# Morpheus_middle.net
KiCad netlist of a schematic drawn in Altium Designer
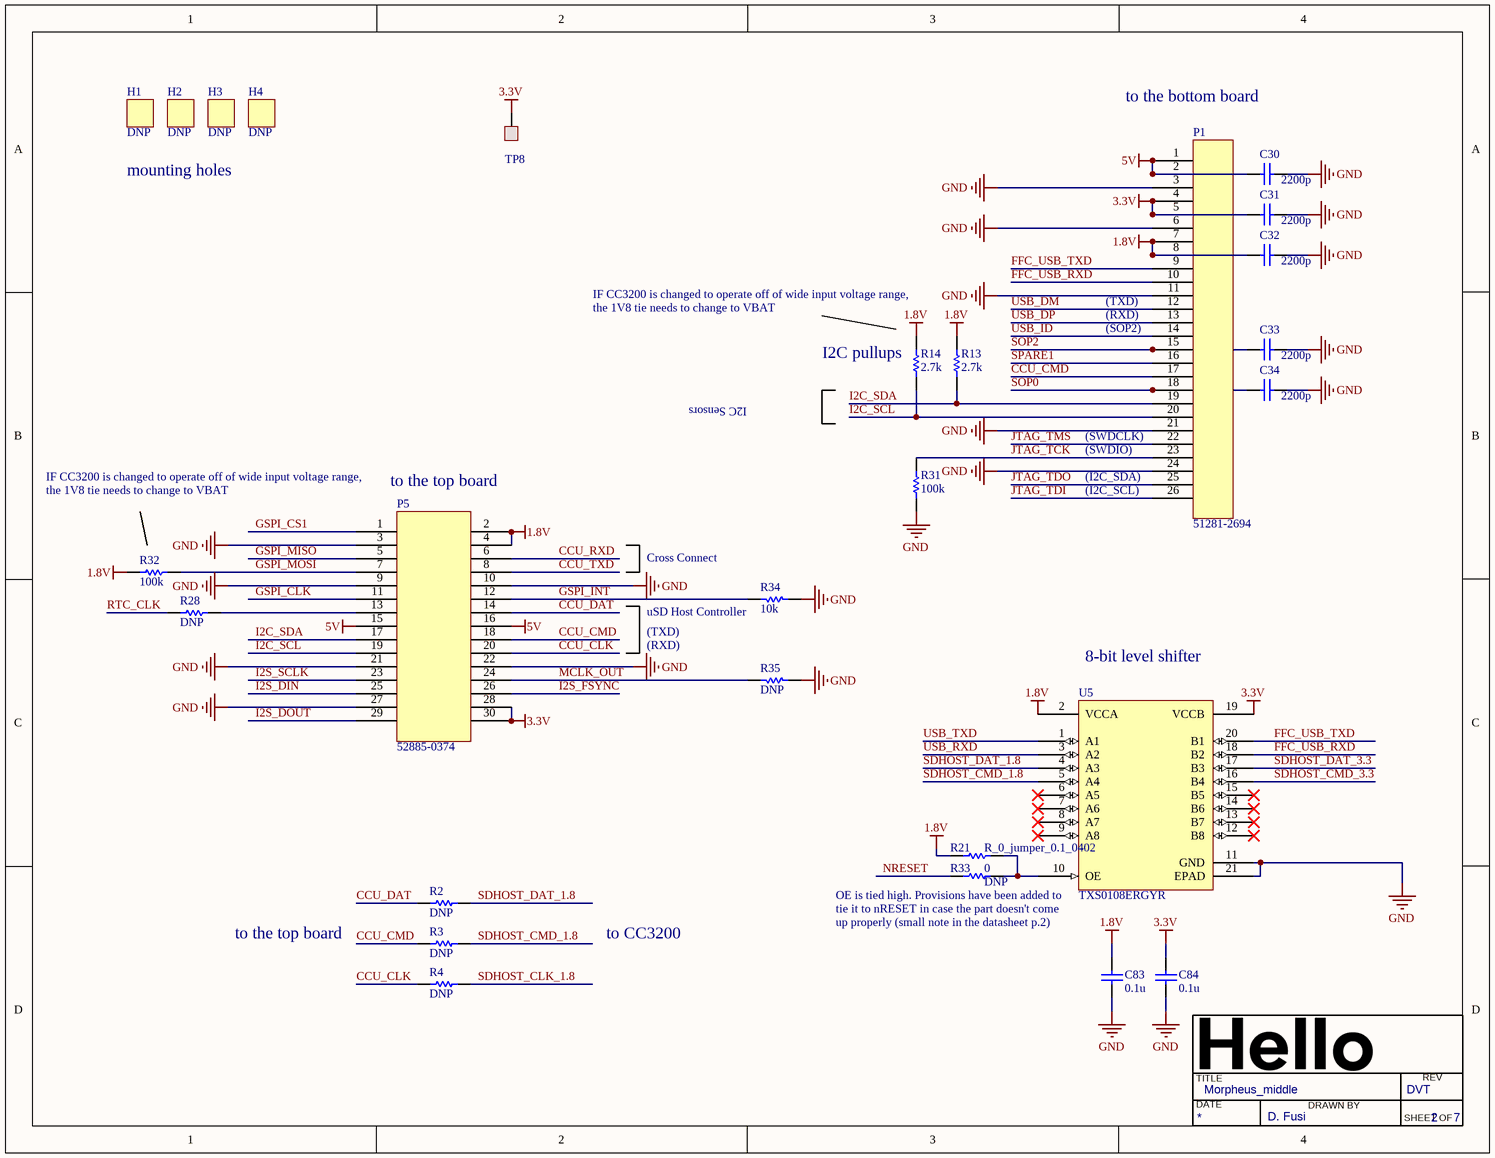
[diagram p0: Morpheus_middle.SchDoc]

(export (version "E")
  (design (tool "Eeschema 10.0.6"))
  (components
    (comp (ref "C30")
      (value "2200p")
      (footprint "CAP0402_SENSE_DVT")
      (description "Chip capacitor")
      (fields (field (name "TOLERANCE") "5 %") (field (name "VOLTAGE") "16V"))
      (libsource (lib "Morpheus_pill") (part "C_2200p_5_16_STD_0402"))
    )
    (comp (ref "C31")
      (value "2200p")
      (footprint "CAP0402_SENSE_DVT")
      (description "Chip capacitor")
      (fields (field (name "TOLERANCE") "5 %") (field (name "VOLTAGE") "16V"))
      (libsource (lib "Morpheus_pill") (part "C_2200p_5_16_STD_0402"))
    )
    (comp (ref "C32")
      (value "2200p")
      (footprint "CAP0402_SENSE_DVT")
      (description "Chip capacitor")
      (fields (field (name "TOLERANCE") "5 %") (field (name "VOLTAGE") "16V"))
      (libsource (lib "Morpheus_pill") (part "C_2200p_5_16_STD_0402"))
    )
    (comp (ref "C33")
      (value "2200p")
      (footprint "CAP0402_SENSE_DVT")
      (description "Chip capacitor")
      (fields (field (name "TOLERANCE") "5 %") (field (name "VOLTAGE") "16V"))
      (libsource (lib "Morpheus_pill") (part "C_2200p_5_16_STD_0402"))
    )
    (comp (ref "C34")
      (value "2200p")
      (footprint "CAP0402_SENSE_DVT")
      (description "Chip capacitor")
      (fields (field (name "TOLERANCE") "5 %") (field (name "VOLTAGE") "16V"))
      (libsource (lib "Morpheus_pill") (part "C_2200p_5_16_STD_0402"))
    )
    (comp (ref "C83")
      (value "0.1u")
      (footprint "CAP0402_SENSE_DVT")
      (description "Chip capacitor")
      (fields (field (name "TOLERANCE") "10%") (field (name "VOLTAGE") "50V"))
      (libsource (lib "Morpheus_pill") (part "C_0.1u_10_50_X7R_0402"))
    )
    (comp (ref "C84")
      (value "0.1u")
      (footprint "CAP0402_SENSE_DVT")
      (description "Chip capacitor")
      (fields (field (name "TOLERANCE") "10%") (field (name "VOLTAGE") "50V"))
      (libsource (lib "Morpheus_pill") (part "C_0.1u_10_50_X7R_0402"))
    )
    (comp (ref "H1")
      (value "DNP")
      (footprint "HOLE_ROUND_1.8mm")
      (description "general purpose hole")
      (libsource (lib "Morpheus_pill") (part "Hole"))
    )
    (comp (ref "H2")
      (value "DNP")
      (footprint "HOLE_ROUND_1.8mm")
      (description "general purpose hole")
      (libsource (lib "Morpheus_pill") (part "Hole"))
    )
    (comp (ref "H3")
      (value "DNP")
      (footprint "HOLE_ROUND_1.8mm")
      (description "general purpose hole")
      (libsource (lib "Morpheus_pill") (part "Hole"))
    )
    (comp (ref "H4")
      (value "DNP")
      (footprint "HOLE_ROUND_1.8mm")
      (description "general purpose hole")
      (libsource (lib "Morpheus_pill") (part "Hole"))
    )
    (comp (ref "P1")
      (value "51281-2694")
      (footprint "molex_51281-2694")
      (description "Molex 26-pin 0.5mm pitch connector")
      (libsource (lib "Morpheus_pill") (part "molex_51281-2694"))
    )
    (comp (ref "P5")
      (value "52885-0374")
      (footprint "molex_52885-0374")
      (description "Molex 30-pin 0.635mm pitch receptacle connector")
      (libsource (lib "Morpheus_pill") (part "molex_52885-0374"))
    )
    (comp (ref "R2")
      (value "DNP")
      (footprint "RES0402-SENSE-DVT")
      (description "Chip Resistor")
      (fields (field (name "TOLERANCE") "Jumper") (field (name "POWER") "0.1 W"))
      (libsource (lib "Morpheus_pill") (part "R_0_jumper_0.1_0402"))
    )
    (comp (ref "R3")
      (value "DNP")
      (footprint "RES0402-SENSE-DVT")
      (description "Chip Resistor")
      (fields (field (name "TOLERANCE") "Jumper") (field (name "POWER") "0.1 W"))
      (libsource (lib "Morpheus_pill") (part "R_0_jumper_0.1_0402"))
    )
    (comp (ref "R4")
      (value "DNP")
      (footprint "RES0402-SENSE-DVT")
      (description "Chip Resistor")
      (fields (field (name "TOLERANCE") "Jumper") (field (name "POWER") "0.1 W"))
      (libsource (lib "Morpheus_pill") (part "R_0_jumper_0.1_0402"))
    )
    (comp (ref "R13")
      (value "2.7k")
      (footprint "RES0402_SENSE_DVT")
      (description "Chip Resistor")
      (fields (field (name "TOLERANCE") "5 %") (field (name "POWER") "0.1 W"))
      (libsource (lib "Morpheus_pill") (part "R_2.7k_5_0.1_0402"))
    )
    (comp (ref "R14")
      (value "2.7k")
      (footprint "RES0402_SENSE_DVT")
      (description "Chip Resistor")
      (fields (field (name "TOLERANCE") "5 %") (field (name "POWER") "0.1 W"))
      (libsource (lib "Morpheus_pill") (part "R_2.7k_5_0.1_0402"))
    )
    (comp (ref "R21")
      (value "R_0_jumper_0.1_0402")
      (footprint "RES0402-SENSE-DVT")
      (description "Chip Resistor")
      (fields (field (name "TOLERANCE") "Jumper") (field (name "POWER") "0.1 W"))
      (libsource (lib "Morpheus_pill") (part "R_0_jumper_0.1_0402"))
    )
    (comp (ref "R28")
      (value "DNP")
      (footprint "RES0402-SENSE-DVT")
      (description "Chip Resistor")
      (fields (field (name "TOLERANCE") "Jumper") (field (name "POWER") "0.1 W"))
      (libsource (lib "Morpheus_pill") (part "R_0_jumper_0.1_0402"))
    )
    (comp (ref "R31")
      (value "100k")
      (footprint "RES0402_SENSE_DVT")
      (description "Chip Resistor")
      (fields (field (name "TOLERANCE") "1 %") (field (name "POWER") "0.1 W"))
      (libsource (lib "Morpheus_pill") (part "R_100k_1_0.1_0402"))
    )
    (comp (ref "R32")
      (value "100k")
      (footprint "RES0402_SENSE_DVT")
      (description "Chip Resistor")
      (fields (field (name "TOLERANCE") "1 %") (field (name "POWER") "0.1 W"))
      (libsource (lib "Morpheus_pill") (part "R_100k_1_0.1_0402"))
    )
    (comp (ref "R33")
      (value "DNP")
      (footprint "RES0402-SENSE-DVT")
      (description "Chip Resistor")
      (fields
        (field (name "ALTIUM_VALUE") "0")
        (field (name "TOLERANCE") "Jumper")
        (field (name "POWER") "0.1 W")
      )
      (libsource (lib "Morpheus_pill") (part "R_0_jumper_0.1_0402"))
    )
    (comp (ref "R34")
      (value "10k")
      (footprint "RES0402_SENSE_DVT")
      (description "Chip Resistor")
      (fields (field (name "TOLERANCE") "5 %") (field (name "POWER") "0.1 W"))
      (libsource (lib "Morpheus_pill") (part "R_10k_5_0.1_0402"))
    )
    (comp (ref "R35")
      (value "DNP")
      (footprint "RES0402_SENSE_DVT")
      (description "Chip Resistor")
      (fields (field (name "TOLERANCE") "5 %") (field (name "POWER") "0.1 W"))
      (libsource (lib "Morpheus_pill") (part "R_10k_5_0.1_0402"))
    )
    (comp (ref "TP8")
      (value "TP")
      (footprint "TP-1.1")
      (description "testpoint")
      (libsource (lib "Morpheus_pill") (part "TP"))
    )
    (comp (ref "U5")
      (value "TXS0108ERGYR")
      (footprint "QFN50P450X350X100_HS-21N")
      (description "8-BIT BIDIRECTIONAL VOLTAGE-LEVEL TRANSLATOR  FOR OPEN-DRAIN AND PUSH-PULL APPLICATIONS")
      (libsource (lib "Morpheus_pill") (part "TXS0108ERGYR"))
    )
  )
  (nets
    (net (code "1") (name "/CCU_CLK") (class "Default")
      (node (ref "P5") (pin "20") (pintype "passive"))
      (node (ref "R4") (pin "1") (pinfunction "1_1") (pintype "passive"))
    )
    (net (code "2") (name "/CCU_CMD") (class "Default")
      (node (ref "P1") (pin "17") (pintype "passive"))
      (node (ref "P5") (pin "18") (pintype "passive"))
      (node (ref "R3") (pin "1") (pinfunction "1_1") (pintype "passive"))
    )
    (net (code "3") (name "/CCU_DAT") (class "Default")
      (node (ref "P5") (pin "14") (pintype "passive"))
      (node (ref "R2") (pin "1") (pinfunction "1_1") (pintype "passive"))
    )
    (net (code "4") (name "/CCU_RXD") (class "Default") (node (ref "P5") (pin "6") (pintype "passive")))
    (net (code "5") (name "/CCU_TXD") (class "Default") (node (ref "P5") (pin "8") (pintype "passive")))
    (net (code "6") (name "/FFC_USB_RXD") (class "Default")
      (node (ref "P1") (pin "10") (pintype "passive"))
      (node (ref "U5") (pin "18") (pinfunction "B2_18") (pintype "bidirectional"))
    )
    (net (code "7") (name "/FFC_USB_TXD") (class "Default")
      (node (ref "P1") (pin "9") (pintype "passive"))
      (node (ref "U5") (pin "20") (pinfunction "B1_20") (pintype "bidirectional"))
    )
    (net (code "8") (name "/GSPI_CLK") (class "Default") (node (ref "P5") (pin "11") (pintype "passive")))
    (net (code "9") (name "/GSPI_CS1") (class "Default") (node (ref "P5") (pin "1") (pintype "passive")))
    (net (code "10") (name "/GSPI_INT") (class "Default")
      (node (ref "P5") (pin "12") (pintype "passive"))
      (node (ref "R34") (pin "1") (pinfunction "1_1") (pintype "passive"))
    )
    (net (code "11") (name "/GSPI_MISO") (class "Default") (node (ref "P5") (pin "5") (pintype "passive")))
    (net (code "12") (name "/GSPI_MOSI") (class "Default")
      (node (ref "P5") (pin "7") (pintype "passive"))
      (node (ref "R32") (pin "1") (pinfunction "1_1") (pintype "passive"))
    )
    (net (code "13") (name "/I2C_SCL") (class "Default")
      (node (ref "P1") (pin "20") (pintype "passive"))
      (node (ref "P5") (pin "19") (pintype "passive"))
      (node (ref "R14") (pin "1") (pinfunction "1_1") (pintype "passive"))
    )
    (net (code "14") (name "/I2C_SDA") (class "Default")
      (node (ref "P1") (pin "19") (pintype "passive"))
      (node (ref "P5") (pin "17") (pintype "passive"))
      (node (ref "R13") (pin "1") (pinfunction "1_1") (pintype "passive"))
    )
    (net (code "15") (name "/I2S_DIN") (class "Default") (node (ref "P5") (pin "25") (pintype "passive")))
    (net (code "16") (name "/I2S_DOUT") (class "Default") (node (ref "P5") (pin "29") (pintype "passive")))
    (net (code "17") (name "/I2S_FSYNC") (class "Default") (node (ref "P5") (pin "26") (pintype "passive")))
    (net (code "18") (name "/I2S_SCLK") (class "Default") (node (ref "P5") (pin "23") (pintype "passive")))
    (net (code "19") (name "/JTAG_TCK") (class "Default")
      (node (ref "P1") (pin "23") (pintype "passive"))
      (node (ref "R31") (pin "2") (pinfunction "2_2") (pintype "passive"))
    )
    (net (code "20") (name "/JTAG_TDI") (class "Default") (node (ref "P1") (pin "26") (pintype "passive")))
    (net (code "21") (name "/JTAG_TDO") (class "Default") (node (ref "P1") (pin "25") (pintype "passive")))
    (net (code "22") (name "/JTAG_TMS") (class "Default") (node (ref "P1") (pin "22") (pintype "passive")))
    (net (code "23") (name "/MCLK_OUT") (class "Default")
      (node (ref "P5") (pin "24") (pintype "passive"))
      (node (ref "R35") (pin "1") (pinfunction "1_1") (pintype "passive"))
    )
    (net (code "24") (name "/NRESET") (class "Default")
      (node (ref "R33") (pin "1") (pinfunction "1_1") (pintype "passive"))
    )
    (net (code "25") (name "/RTC_CLK") (class "Default")
      (node (ref "R28") (pin "1") (pinfunction "1_1") (pintype "passive"))
    )
    (net (code "26") (name "/SDHOST_CLK_1.8") (class "Default")
      (node (ref "R4") (pin "2") (pinfunction "2_2") (pintype "passive"))
    )
    (net (code "27") (name "/SDHOST_CMD_1.8") (class "Default")
      (node (ref "R3") (pin "2") (pinfunction "2_2") (pintype "passive"))
      (node (ref "U5") (pin "5") (pinfunction "A4_5") (pintype "bidirectional"))
    )
    (net (code "28") (name "/SDHOST_CMD_3.3") (class "Default")
      (node (ref "U5") (pin "16") (pinfunction "B4_16") (pintype "bidirectional"))
    )
    (net (code "29") (name "/SDHOST_DAT_1.8") (class "Default")
      (node (ref "R2") (pin "2") (pinfunction "2_2") (pintype "passive"))
      (node (ref "U5") (pin "4") (pinfunction "A3_4") (pintype "bidirectional"))
    )
    (net (code "30") (name "/SDHOST_DAT_3.3") (class "Default")
      (node (ref "U5") (pin "17") (pinfunction "B3_17") (pintype "bidirectional"))
    )
    (net (code "31") (name "/SOP0") (class "Default")
      (node (ref "C34") (pin "1") (pinfunction "1_1") (pintype "passive"))
      (node (ref "P1") (pin "18") (pintype "passive"))
    )
    (net (code "32") (name "/SOP2") (class "Default")
      (node (ref "C33") (pin "1") (pinfunction "1_1") (pintype "passive"))
      (node (ref "P1") (pin "15") (pintype "passive"))
    )
    (net (code "33") (name "/SPARE1") (class "Default") (node (ref "P1") (pin "16") (pintype "passive")))
    (net (code "34") (name "/USB_DM") (class "Default") (node (ref "P1") (pin "12") (pintype "passive")))
    (net (code "35") (name "/USB_DP") (class "Default") (node (ref "P1") (pin "13") (pintype "passive")))
    (net (code "36") (name "/USB_ID") (class "Default") (node (ref "P1") (pin "14") (pintype "passive")))
    (net (code "37") (name "/USB_RXD") (class "Default")
      (node (ref "U5") (pin "3") (pinfunction "A2_3") (pintype "bidirectional"))
    )
    (net (code "38") (name "/USB_TXD") (class "Default")
      (node (ref "U5") (pin "1") (pinfunction "A1_1") (pintype "bidirectional"))
    )
    (net (code "39") (name "1.8V") (class "Default")
      (node (ref "C32") (pin "1") (pinfunction "1_1") (pintype "passive"))
      (node (ref "C83") (pin "2") (pinfunction "2_2") (pintype "passive"))
      (node (ref "P1") (pin "7") (pintype "passive"))
      (node (ref "P1") (pin "8") (pintype "passive"))
      (node (ref "P5") (pin "2") (pintype "passive"))
      (node (ref "P5") (pin "4") (pintype "passive"))
      (node (ref "R13") (pin "2") (pinfunction "2_2") (pintype "passive"))
      (node (ref "R14") (pin "2") (pinfunction "2_2") (pintype "passive"))
      (node (ref "R21") (pin "1") (pinfunction "1_1") (pintype "passive"))
      (node (ref "R32") (pin "2") (pinfunction "2_2") (pintype "passive"))
      (node (ref "U5") (pin "2") (pinfunction "VCCA_2") (pintype "power_in"))
    )
    (net (code "40") (name "3.3V") (class "Default")
      (node (ref "C31") (pin "1") (pinfunction "1_1") (pintype "passive"))
      (node (ref "C84") (pin "2") (pinfunction "2_2") (pintype "passive"))
      (node (ref "P1") (pin "4") (pintype "passive"))
      (node (ref "P1") (pin "5") (pintype "passive"))
      (node (ref "P5") (pin "28") (pintype "passive"))
      (node (ref "P5") (pin "30") (pintype "passive"))
      (node (ref "TP8") (pin "1") (pinfunction "1_1") (pintype "passive"))
      (node (ref "U5") (pin "19") (pinfunction "VCCB_19") (pintype "power_in"))
    )
    (net (code "41") (name "5V") (class "Default")
      (node (ref "C30") (pin "1") (pinfunction "1_1") (pintype "passive"))
      (node (ref "P1") (pin "1") (pintype "passive"))
      (node (ref "P1") (pin "2") (pintype "passive"))
      (node (ref "P5") (pin "15") (pintype "passive"))
      (node (ref "P5") (pin "16") (pintype "passive"))
    )
    (net (code "42") (name "GND") (class "Default")
      (node (ref "C30") (pin "2") (pinfunction "2_2") (pintype "passive"))
      (node (ref "C31") (pin "2") (pinfunction "2_2") (pintype "passive"))
      (node (ref "C32") (pin "2") (pinfunction "2_2") (pintype "passive"))
      (node (ref "C33") (pin "2") (pinfunction "2_2") (pintype "passive"))
      (node (ref "C34") (pin "2") (pinfunction "2_2") (pintype "passive"))
      (node (ref "C83") (pin "1") (pinfunction "1_1") (pintype "passive"))
      (node (ref "C84") (pin "1") (pinfunction "1_1") (pintype "passive"))
      (node (ref "P1") (pin "11") (pintype "passive"))
      (node (ref "P1") (pin "21") (pintype "passive"))
      (node (ref "P1") (pin "24") (pintype "passive"))
      (node (ref "P1") (pin "3") (pintype "passive"))
      (node (ref "P1") (pin "6") (pintype "passive"))
      (node (ref "P5") (pin "10") (pintype "passive"))
      (node (ref "P5") (pin "21") (pintype "passive"))
      (node (ref "P5") (pin "22") (pintype "passive"))
      (node (ref "P5") (pin "27") (pintype "passive"))
      (node (ref "P5") (pin "3") (pintype "passive"))
      (node (ref "P5") (pin "9") (pintype "passive"))
      (node (ref "R31") (pin "1") (pinfunction "1_1") (pintype "passive"))
      (node (ref "R34") (pin "2") (pinfunction "2_2") (pintype "passive"))
      (node (ref "R35") (pin "2") (pinfunction "2_2") (pintype "passive"))
      (node (ref "U5") (pin "11") (pinfunction "GND_11") (pintype "power_in"))
      (node (ref "U5") (pin "21") (pinfunction "EPAD_21") (pintype "passive"))
    )
    (net (code "43") (name "Net-(P5-Pad13)") (class "Default")
      (node (ref "P5") (pin "13") (pintype "passive"))
      (node (ref "R28") (pin "2") (pinfunction "2_2") (pintype "passive"))
    )
    (net (code "44") (name "Net-(U5-OE)") (class "Default")
      (node (ref "R21") (pin "2") (pinfunction "2_2") (pintype "passive"))
      (node (ref "R33") (pin "2") (pinfunction "2_2") (pintype "passive"))
      (node (ref "U5") (pin "10") (pinfunction "OE_10") (pintype "input"))
    )
    (net (code "45") (name "unconnected-(U5-A5-Pad6)") (class "Default")
      (node (ref "U5") (pin "6") (pinfunction "A5_6") (pintype "bidirectional+no_connect"))
    )
    (net (code "46") (name "unconnected-(U5-A6-Pad7)") (class "Default")
      (node (ref "U5") (pin "7") (pinfunction "A6_7") (pintype "bidirectional+no_connect"))
    )
    (net (code "47") (name "unconnected-(U5-A7-Pad8)") (class "Default")
      (node (ref "U5") (pin "8") (pinfunction "A7_8") (pintype "bidirectional+no_connect"))
    )
    (net (code "48") (name "unconnected-(U5-A8-Pad9)") (class "Default")
      (node (ref "U5") (pin "9") (pinfunction "A8_9") (pintype "bidirectional+no_connect"))
    )
    (net (code "49") (name "unconnected-(U5-B5-Pad15)") (class "Default")
      (node (ref "U5") (pin "15") (pinfunction "B5_15") (pintype "bidirectional+no_connect"))
    )
    (net (code "50") (name "unconnected-(U5-B6-Pad14)") (class "Default")
      (node (ref "U5") (pin "14") (pinfunction "B6_14") (pintype "bidirectional+no_connect"))
    )
    (net (code "51") (name "unconnected-(U5-B7-Pad13)") (class "Default")
      (node (ref "U5") (pin "13") (pinfunction "B7_13") (pintype "bidirectional+no_connect"))
    )
    (net (code "52") (name "unconnected-(U5-B8-Pad12)") (class "Default")
      (node (ref "U5") (pin "12") (pinfunction "B8_12") (pintype "bidirectional+no_connect"))
    )
  )
)
